# E17-08-HIU.net
KiCad netlist of a schematic drawn in Altium Designer
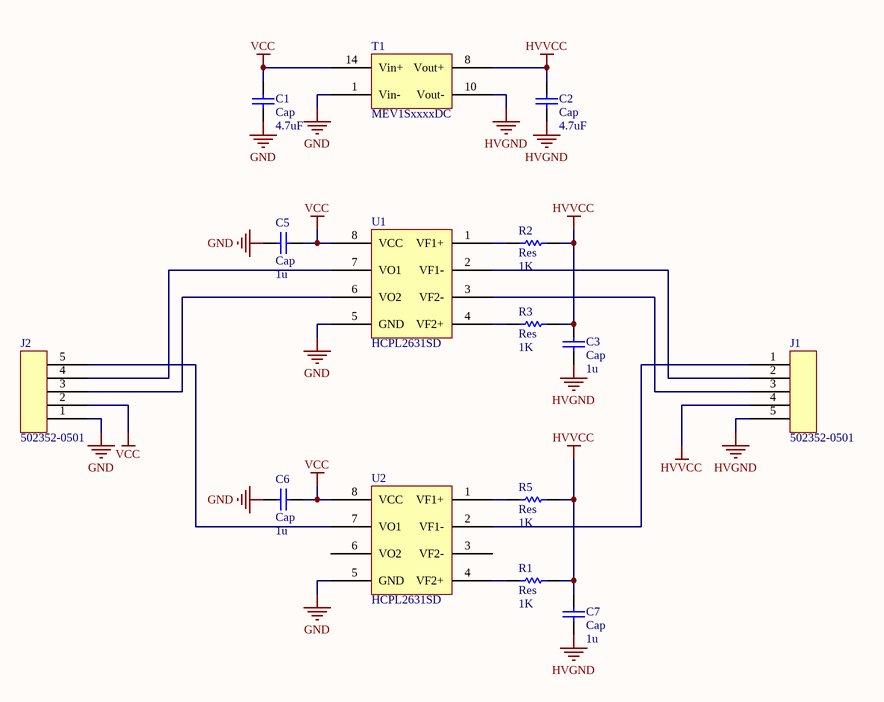
[diagram p0: E17-08-HIU.SchDoc]

(export (version "E")
  (design (tool "Eeschema 10.0.6"))
  (components
    (comp (ref "C1")
      (value "Cap")
      (footprint "C1206")
      (description "Capacitor")
      (fields (field (name "ALTIUM_VALUE") "4.7uF") (field (name "PUBLISHER") "Altium Limited"))
      (libsource (lib "Capacitors") (part "Cap"))
    )
    (comp (ref "C2")
      (value "Cap")
      (footprint "C1206")
      (description "Capacitor")
      (fields (field (name "ALTIUM_VALUE") "4.7uF") (field (name "PUBLISHER") "Altium Limited"))
      (libsource (lib "Capacitors") (part "Cap"))
    )
    (comp (ref "C3")
      (value "Cap")
      (footprint "C0805")
      (description "Capacitor")
      (fields (field (name "ALTIUM_VALUE") "1u") (field (name "PUBLISHER") "Altium Limited"))
      (libsource (lib "Capacitors") (part "Cap"))
    )
    (comp (ref "C5")
      (value "Cap")
      (footprint "C0805")
      (description "Capacitor")
      (fields (field (name "ALTIUM_VALUE") "1u") (field (name "PUBLISHER") "Altium Limited"))
      (libsource (lib "Capacitors") (part "Cap"))
    )
    (comp (ref "C6")
      (value "Cap")
      (footprint "C0805")
      (description "Capacitor")
      (fields (field (name "ALTIUM_VALUE") "1u") (field (name "PUBLISHER") "Altium Limited"))
      (libsource (lib "Capacitors") (part "Cap"))
    )
    (comp (ref "C7")
      (value "Cap")
      (footprint "C0805")
      (description "Capacitor")
      (fields (field (name "ALTIUM_VALUE") "1u") (field (name "PUBLISHER") "Altium Limited"))
      (libsource (lib "Capacitors") (part "Cap"))
    )
    (comp (ref "J1")
      (value "502352-0501")
      (footprint "502352-0501")
      (libsource (lib "Connectors and Headers") (part "502352-0501"))
    )
    (comp (ref "J2")
      (value "502352-0501")
      (footprint "502352-0501")
      (libsource (lib "") (part "502352-0501_1"))
    )
    (comp (ref "R1")
      (value "Res")
      (footprint "2012[0805]")
      (description "Surface Mount Resistor")
      (fields (field (name "ALTIUM_VALUE") "1K") (field (name "PUBLISHER") "Altium Limited"))
      (libsource (lib "Resistors") (part "Res"))
    )
    (comp (ref "R2")
      (value "Res")
      (footprint "2012[0805]")
      (description "Surface Mount Resistor")
      (fields (field (name "ALTIUM_VALUE") "1K") (field (name "PUBLISHER") "Altium Limited"))
      (libsource (lib "Resistors") (part "Res"))
    )
    (comp (ref "R3")
      (value "Res")
      (footprint "2012[0805]")
      (description "Surface Mount Resistor")
      (fields (field (name "ALTIUM_VALUE") "1K") (field (name "PUBLISHER") "Altium Limited"))
      (libsource (lib "Resistors") (part "Res"))
    )
    (comp (ref "R5")
      (value "Res")
      (footprint "2012[0805]")
      (description "Surface Mount Resistor")
      (fields (field (name "ALTIUM_VALUE") "1K") (field (name "PUBLISHER") "Altium Limited"))
      (libsource (lib "Resistors") (part "Res"))
    )
    (comp (ref "T1")
      (value "MEV1SxxxxDC")
      (footprint "MEV1SxxxxDC")
      (libsource (lib "Voltage Regulation") (part "MEV1SxxxxDC"))
    )
    (comp (ref "U1")
      (value "HCPL2631SD")
      (footprint "HCPL2631SD")
      (libsource (lib "Isolation Circuits") (part "HCPL2631SD"))
    )
    (comp (ref "U2")
      (value "HCPL2631SD")
      (footprint "HCPL2631SD")
      (libsource (lib "Isolation Circuits") (part "HCPL2631SD"))
    )
  )
  (nets
    (net (code "1") (name "GND") (class "Default")
      (node (ref "C1") (pin "1") (pinfunction "1_1") (pintype "passive"))
      (node (ref "C5") (pin "1") (pinfunction "1_1") (pintype "passive"))
      (node (ref "C6") (pin "1") (pinfunction "1_1") (pintype "passive"))
      (node (ref "J2") (pin "1") (pinfunction "1_1") (pintype "passive"))
      (node (ref "T1") (pin "1") (pinfunction "Vin-_1") (pintype "passive"))
      (node (ref "U1") (pin "5") (pinfunction "GND_5") (pintype "passive"))
      (node (ref "U2") (pin "5") (pinfunction "GND_5") (pintype "passive"))
    )
    (net (code "2") (name "HVGND") (class "Default")
      (node (ref "C2") (pin "1") (pinfunction "1_1") (pintype "passive"))
      (node (ref "C3") (pin "1") (pinfunction "1_1") (pintype "passive"))
      (node (ref "C7") (pin "1") (pinfunction "1_1") (pintype "passive"))
      (node (ref "J1") (pin "5") (pinfunction "5_5") (pintype "passive"))
      (node (ref "T1") (pin "10") (pinfunction "Vout-_10") (pintype "passive"))
    )
    (net (code "3") (name "HVVCC") (class "Default")
      (node (ref "C2") (pin "2") (pinfunction "2_2") (pintype "passive"))
      (node (ref "C3") (pin "2") (pinfunction "2_2") (pintype "passive"))
      (node (ref "C7") (pin "2") (pinfunction "2_2") (pintype "passive"))
      (node (ref "J1") (pin "4") (pinfunction "4_4") (pintype "passive"))
      (node (ref "R1") (pin "2") (pinfunction "2_2") (pintype "passive"))
      (node (ref "R2") (pin "2") (pinfunction "2_2") (pintype "passive"))
      (node (ref "R3") (pin "2") (pinfunction "2_2") (pintype "passive"))
      (node (ref "R5") (pin "2") (pinfunction "2_2") (pintype "passive"))
      (node (ref "T1") (pin "8") (pinfunction "Vout+_8") (pintype "passive"))
    )
    (net (code "4") (name "Net-(U1-VF1+)") (class "Default")
      (node (ref "R2") (pin "1") (pinfunction "1_1") (pintype "passive"))
      (node (ref "U1") (pin "1") (pinfunction "VF1+_1") (pintype "passive"))
    )
    (net (code "5") (name "Net-(U1-VF1-)") (class "Default")
      (node (ref "J1") (pin "2") (pinfunction "2_2") (pintype "passive"))
      (node (ref "U1") (pin "2") (pinfunction "VF1-_2") (pintype "passive"))
    )
    (net (code "6") (name "Net-(U1-VF2+)") (class "Default")
      (node (ref "R3") (pin "1") (pinfunction "1_1") (pintype "passive"))
      (node (ref "U1") (pin "4") (pinfunction "VF2+_4") (pintype "passive"))
    )
    (net (code "7") (name "Net-(U1-VF2-)") (class "Default")
      (node (ref "J1") (pin "3") (pinfunction "3_3") (pintype "passive"))
      (node (ref "U1") (pin "3") (pinfunction "VF2-_3") (pintype "passive"))
    )
    (net (code "8") (name "Net-(U1-VO1)") (class "Default")
      (node (ref "J2") (pin "4") (pinfunction "4_4") (pintype "passive"))
      (node (ref "U1") (pin "7") (pinfunction "VO1_7") (pintype "passive"))
    )
    (net (code "9") (name "Net-(U1-VO2)") (class "Default")
      (node (ref "J2") (pin "3") (pinfunction "3_3") (pintype "passive"))
      (node (ref "U1") (pin "6") (pinfunction "VO2_6") (pintype "passive"))
    )
    (net (code "10") (name "Net-(U2-VF1+)") (class "Default")
      (node (ref "R5") (pin "1") (pinfunction "1_1") (pintype "passive"))
      (node (ref "U2") (pin "1") (pinfunction "VF1+_1") (pintype "passive"))
    )
    (net (code "11") (name "Net-(U2-VF1-)") (class "Default")
      (node (ref "J1") (pin "1") (pinfunction "1_1") (pintype "passive"))
      (node (ref "U2") (pin "2") (pinfunction "VF1-_2") (pintype "passive"))
    )
    (net (code "12") (name "Net-(U2-VF2+)") (class "Default")
      (node (ref "R1") (pin "1") (pinfunction "1_1") (pintype "passive"))
      (node (ref "U2") (pin "4") (pinfunction "VF2+_4") (pintype "passive"))
    )
    (net (code "13") (name "Net-(U2-VO1)") (class "Default")
      (node (ref "J2") (pin "5") (pinfunction "5_5") (pintype "passive"))
      (node (ref "U2") (pin "7") (pinfunction "VO1_7") (pintype "passive"))
    )
    (net (code "14") (name "VCC") (class "Default")
      (node (ref "C1") (pin "2") (pinfunction "2_2") (pintype "passive"))
      (node (ref "C5") (pin "2") (pinfunction "2_2") (pintype "passive"))
      (node (ref "C6") (pin "2") (pinfunction "2_2") (pintype "passive"))
      (node (ref "J2") (pin "2") (pinfunction "2_2") (pintype "passive"))
      (node (ref "T1") (pin "14") (pinfunction "Vin+_14") (pintype "passive"))
      (node (ref "U1") (pin "8") (pinfunction "VCC_8") (pintype "passive"))
      (node (ref "U2") (pin "8") (pinfunction "VCC_8") (pintype "passive"))
    )
    (net (code "15") (name "unconnected-(U2-VF2--Pad3)") (class "Default")
      (node (ref "U2") (pin "3") (pinfunction "VF2-_3") (pintype "passive"))
    )
    (net (code "16") (name "unconnected-(U2-VO2-Pad6)") (class "Default")
      (node (ref "U2") (pin "6") (pinfunction "VO2_6") (pintype "passive"))
    )
  )
)
